# DE-180824.net
KiCad netlist of a schematic drawn in Altium Designer
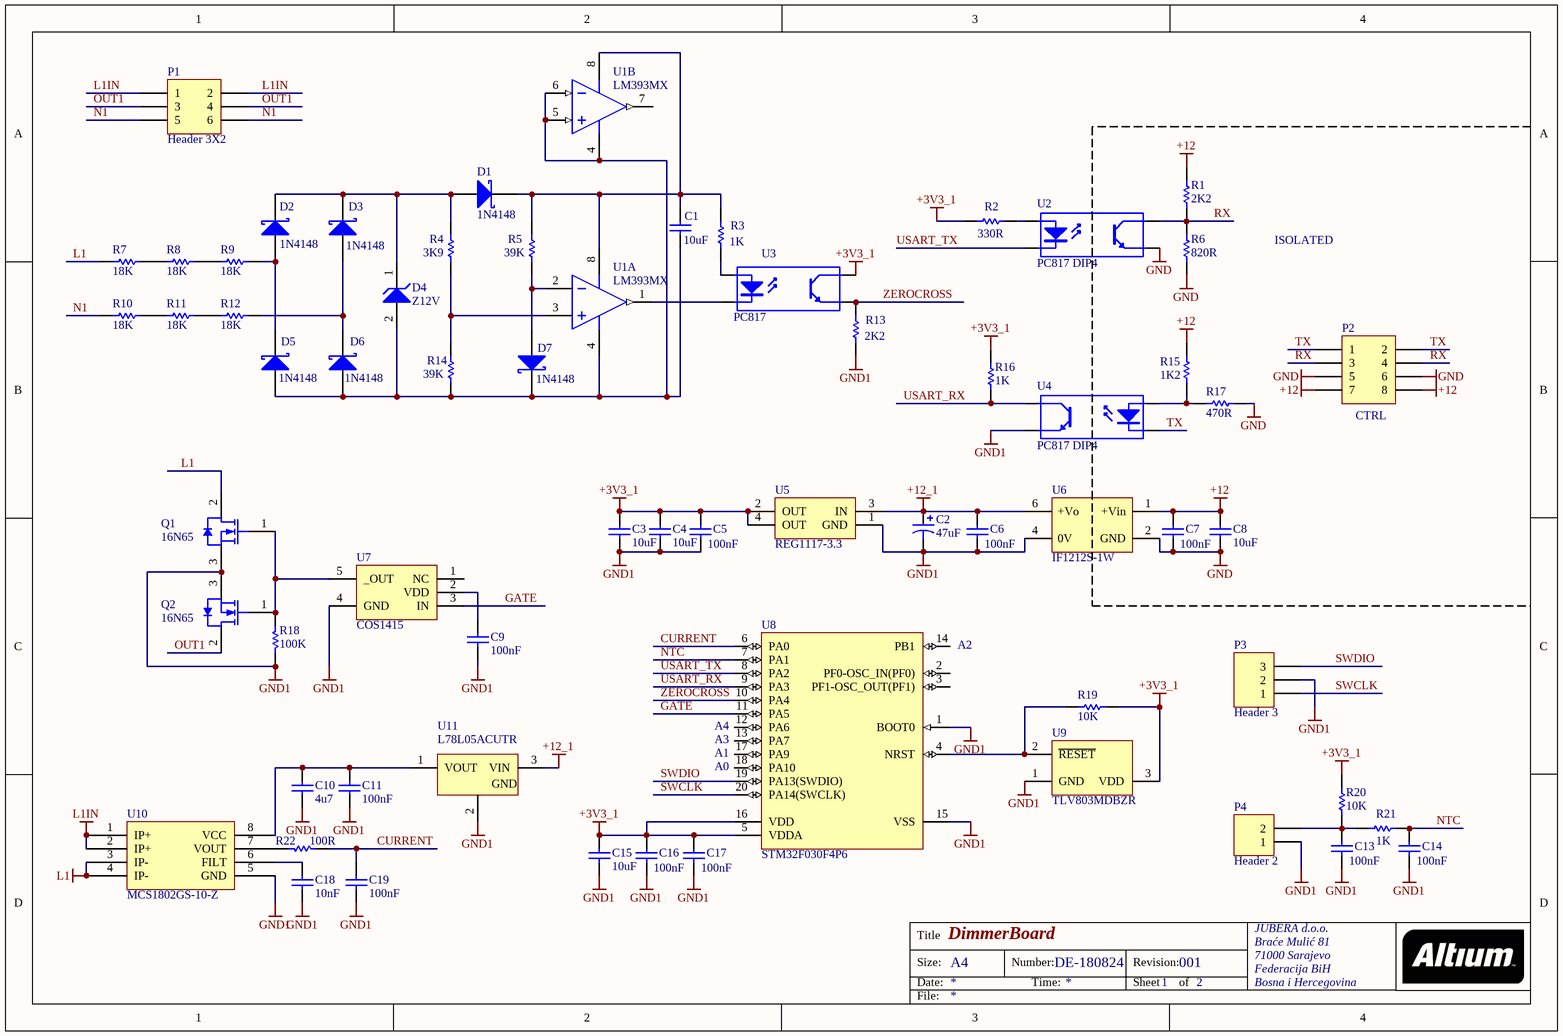
[diagram p0: DE-180824.SchDoc]

(export (version "E")
  (design (tool "Eeschema 10.0.6"))
  (components
    (comp (ref "C1")
      (value "10uF")
      (footprint "0805")
      (description "Ceramic Chip Capacitor - Standard")
      (fields (field (name "PUBLISHER") "Altium Limited"))
      (libsource (lib "DE-100224") (part "C0805"))
    )
    (comp (ref "C2")
      (value "47uF")
      (footprint "H")
      (fields (field (name "PUBLISHER") "Altium Limited"))
      (libsource (lib "Vishay Sprague Tantalum Chip Capacitor") (part "194D476X0015H2"))
    )
    (comp (ref "C3")
      (value "10uF")
      (footprint "0805")
      (description "Ceramic Chip Capacitor - Standard")
      (fields (field (name "Comment") "C0805") (field (name "PUBLISHER") "Altium Limited"))
      (libsource (lib "DE-180824") (part "C0805"))
    )
    (comp (ref "C4")
      (value "10uF")
      (footprint "0805")
      (description "Ceramic Chip Capacitor - Standard")
      (fields (field (name "Comment") "C0805") (field (name "PUBLISHER") "Altium Limited"))
      (libsource (lib "DE-180824") (part "C0805"))
    )
    (comp (ref "C5")
      (value "100nF")
      (footprint "0603")
      (description "Ceramic Chip Capacitor - Standard")
      (fields (field (name "Comment") "C0603") (field (name "PUBLISHER") "Altium Limited"))
      (libsource (lib "DE-180824") (part "C0603"))
    )
    (comp (ref "C6")
      (value "100nF")
      (footprint "0603")
      (description "Ceramic Chip Capacitor - Standard")
      (fields (field (name "Comment") "C0603") (field (name "PUBLISHER") "Altium Limited"))
      (libsource (lib "DE-180824") (part "C0603"))
    )
    (comp (ref "C7")
      (value "100nF")
      (footprint "0603")
      (description "Ceramic Chip Capacitor - Standard")
      (fields (field (name "Comment") "C0603") (field (name "PUBLISHER") "Altium Limited"))
      (libsource (lib "DE-180824") (part "C0603"))
    )
    (comp (ref "C8")
      (value "10uF")
      (footprint "0805")
      (description "Ceramic Chip Capacitor - Standard")
      (fields (field (name "Comment") "C0805") (field (name "PUBLISHER") "Altium Limited"))
      (libsource (lib "DE-180824") (part "C0805"))
    )
    (comp (ref "C9")
      (value "100nF")
      (footprint "0603")
      (description "Ceramic Chip Capacitor - Standard")
      (fields (field (name "Comment") "C0603") (field (name "PUBLISHER") "Altium Limited"))
      (libsource (lib "DE-180824") (part "C0603"))
    )
    (comp (ref "C10")
      (value "4u7")
      (footprint "0805")
      (description "Ceramic Chip Capacitor - Standard")
      (fields (field (name "Comment") "C0805") (field (name "PUBLISHER") "Altium Limited"))
      (libsource (lib "DE-120824") (part "C0805"))
    )
    (comp (ref "C11")
      (value "100nF")
      (footprint "0603")
      (description "Ceramic Chip Capacitor - Standard")
      (fields (field (name "Comment") "C0603") (field (name "PUBLISHER") "Altium Limited"))
      (libsource (lib "DE-120824") (part "C0603"))
    )
    (comp (ref "C13")
      (value "100nF")
      (footprint "0603")
      (description "Ceramic Chip Capacitor - Standard")
      (fields (field (name "Comment") "C0603") (field (name "PUBLISHER") "Altium Limited"))
      (libsource (lib "DE-180824") (part "C0603"))
    )
    (comp (ref "C14")
      (value "100nF")
      (footprint "0603")
      (description "Ceramic Chip Capacitor - Standard")
      (fields (field (name "Comment") "C0603") (field (name "PUBLISHER") "Altium Limited"))
      (libsource (lib "DE-180824") (part "C0603"))
    )
    (comp (ref "C15")
      (value "10uF")
      (footprint "0805")
      (description "Ceramic Chip Capacitor - Standard")
      (fields (field (name "Comment") "C0805") (field (name "PUBLISHER") "Altium Limited"))
      (libsource (lib "DE-180824") (part "C0805"))
    )
    (comp (ref "C16")
      (value "100nF")
      (footprint "0603")
      (description "Ceramic Chip Capacitor - Standard")
      (fields (field (name "Comment") "C0603") (field (name "PUBLISHER") "Altium Limited"))
      (libsource (lib "DE-180824") (part "C0603"))
    )
    (comp (ref "C17")
      (value "100nF")
      (footprint "0603")
      (description "Ceramic Chip Capacitor - Standard")
      (fields (field (name "Comment") "C0603") (field (name "PUBLISHER") "Altium Limited"))
      (libsource (lib "DE-180824") (part "C0603"))
    )
    (comp (ref "C18")
      (value "10nF")
      (footprint "0603")
      (description "Ceramic Chip Capacitor - Standard")
      (fields (field (name "Comment") "C0603") (field (name "PUBLISHER") "Altium Limited"))
      (libsource (lib "DE-120824") (part "C0603"))
    )
    (comp (ref "C19")
      (value "100nF")
      (footprint "0603")
      (description "Ceramic Chip Capacitor - Standard")
      (fields (field (name "Comment") "C0603") (field (name "PUBLISHER") "Altium Limited"))
      (libsource (lib "DE-120824") (part "C0603"))
    )
    (comp (ref "D1")
      (value "1N4148")
      (footprint "SOD323")
      (description "Schottky Barrier Diode")
      (fields (field (name "PUBLISHER") "Altium Limited"))
      (libsource (lib "DE-100224") (part "1PS76SB10"))
    )
    (comp (ref "D2")
      (value "1N4148")
      (footprint "SOD323")
      (description "Schottky Barrier Diode")
      (fields (field (name "PUBLISHER") "Altium Limited"))
      (libsource (lib "DE-100224") (part "1PS76SB10"))
    )
    (comp (ref "D3")
      (value "1N4148")
      (footprint "SOD323")
      (description "Schottky Barrier Diode")
      (fields (field (name "PUBLISHER") "Altium Limited"))
      (libsource (lib "DE-100224") (part "1PS76SB10"))
    )
    (comp (ref "D4")
      (value "Z12V")
      (footprint "ONSC-SOD-323-2-477-02_V")
      (description "Zener Voltage Regulator, 300 mW, 2-Pin SOD-323, Pb-Free, Tape and Reel")
      (fields (field (name "MANUFACTURER") "On Semiconductor") (field (name "PARTNUMBER") "SZMM3Z12VT1G"))
      (libsource (lib "ON Semi Zener Diodes") (part "SZMM3Z12VT1G"))
    )
    (comp (ref "D5")
      (value "1N4148")
      (footprint "SOD323")
      (description "Schottky Barrier Diode")
      (fields (field (name "PUBLISHER") "Altium Limited"))
      (libsource (lib "DE-100224") (part "1PS76SB10"))
    )
    (comp (ref "D6")
      (value "1N4148")
      (footprint "SOD323")
      (description "Schottky Barrier Diode")
      (fields (field (name "PUBLISHER") "Altium Limited"))
      (libsource (lib "DE-100224") (part "1PS76SB10"))
    )
    (comp (ref "D7")
      (value "1N4148")
      (footprint "SOD323")
      (description "Schottky Barrier Diode")
      (fields (field (name "PUBLISHER") "Altium Limited"))
      (libsource (lib "DE-100224") (part "1PS76SB10"))
    )
    (comp (ref "P1")
      (value "Header 3X2")
      (footprint "HDR2X3")
      (description "Header, 3-Pin, Dual row")
      (fields (field (name "PUBLISHER") "Altium Limited"))
      (libsource (lib "Miscellaneous Connectors") (part "Header 3X2"))
    )
    (comp (ref "P2")
      (value "CTRL")
      (footprint "HDR2X4")
      (description "Header, 4-Pin, Dual row")
      (fields (field (name "PUBLISHER") "Altium Limited"))
      (libsource (lib "DE-180824") (part "Header 4X2"))
    )
    (comp (ref "P3")
      (value "Header 3")
      (footprint "HDR1X3")
      (description "Header, 3-Pin")
      (fields (field (name "PUBLISHER") "Altium Limited"))
      (libsource (lib "Miscellaneous Connectors") (part "Header 3"))
    )
    (comp (ref "P4")
      (value "Header 2")
      (footprint "HDR1X2")
      (description "Header, 2-Pin")
      (fields (field (name "PUBLISHER") "Altium Limited"))
      (libsource (lib "Miscellaneous Connectors") (part "Header 2"))
    )
    (comp (ref "Q1")
      (value "16N65")
      (footprint "INF-PG-TO263-3-2_N")
      (fields (field (name "MANUFACTURER") "Infineon") (field (name "PARTNUMBER") "IPB020NE7N3 G"))
      (libsource (lib "Infineon_Power_MOSFET") (part "IPB020NE7N3 G"))
    )
    (comp (ref "Q2")
      (value "16N65")
      (footprint "INF-PG-TO263-3-2_N")
      (fields (field (name "MANUFACTURER") "Infineon") (field (name "PARTNUMBER") "IPB020NE7N3 G"))
      (libsource (lib "Infineon_Power_MOSFET") (part "IPB020NE7N3 G"))
    )
    (comp (ref "R1")
      (value "2K2")
      (footprint "ERA-0603")
      (fields (field (name "PUBLISHER") "Altium Limited"))
      (libsource (lib "DE-100224") (part "ERAV"))
    )
    (comp (ref "R2")
      (value "330R")
      (footprint "ERA-0603")
      (fields (field (name "PUBLISHER") "Altium Limited"))
      (libsource (lib "DE-100224") (part "ERAV"))
    )
    (comp (ref "R3")
      (value "1K")
      (footprint "ERA-0603")
      (fields (field (name "PUBLISHER") "Altium Limited"))
      (libsource (lib "DE-100224") (part "ERAV"))
    )
    (comp (ref "R4")
      (value "3K9")
      (footprint "ERA-0603")
      (fields (field (name "PUBLISHER") "Altium Limited"))
      (libsource (lib "DE-100224") (part "ERAV"))
    )
    (comp (ref "R5")
      (value "39K")
      (footprint "ERA-0603")
      (fields (field (name "PUBLISHER") "Altium Limited"))
      (libsource (lib "DE-100224") (part "ERAV"))
    )
    (comp (ref "R6")
      (value "820R")
      (footprint "ERA-0603")
      (fields (field (name "PUBLISHER") "Altium Limited"))
      (libsource (lib "DE-100224") (part "ERAV"))
    )
    (comp (ref "R7")
      (value "18K")
      (footprint "ERA-0805")
      (fields (field (name "PUBLISHER") "Altium Limited"))
      (libsource (lib "DE-100224") (part "ERAS"))
    )
    (comp (ref "R8")
      (value "18K")
      (footprint "ERA-0805")
      (fields (field (name "PUBLISHER") "Altium Limited"))
      (libsource (lib "DE-100224") (part "ERAS"))
    )
    (comp (ref "R9")
      (value "18K")
      (footprint "ERA-0805")
      (fields (field (name "PUBLISHER") "Altium Limited"))
      (libsource (lib "DE-100224") (part "ERAS"))
    )
    (comp (ref "R10")
      (value "18K")
      (footprint "ERA-0805")
      (fields (field (name "PUBLISHER") "Altium Limited"))
      (libsource (lib "DE-100224") (part "ERAS"))
    )
    (comp (ref "R11")
      (value "18K")
      (footprint "ERA-0805")
      (fields (field (name "PUBLISHER") "Altium Limited"))
      (libsource (lib "DE-100224") (part "ERAS"))
    )
    (comp (ref "R12")
      (value "18K")
      (footprint "ERA-0805")
      (fields (field (name "PUBLISHER") "Altium Limited"))
      (libsource (lib "DE-100224") (part "ERAS"))
    )
    (comp (ref "R13")
      (value "2K2")
      (footprint "ERA-0603")
      (fields (field (name "PUBLISHER") "Altium Limited"))
      (libsource (lib "DE-100224") (part "ERAV"))
    )
    (comp (ref "R14")
      (value "39K")
      (footprint "ERA-0603")
      (fields (field (name "PUBLISHER") "Altium Limited"))
      (libsource (lib "DE-100224") (part "ERAV"))
    )
    (comp (ref "R15")
      (value "1K2")
      (footprint "ERA-0603")
      (fields (field (name "PUBLISHER") "Altium Limited"))
      (libsource (lib "DE-100224") (part "ERAV"))
    )
    (comp (ref "R16")
      (value "1K")
      (footprint "ERA-0603")
      (fields (field (name "PUBLISHER") "Altium Limited"))
      (libsource (lib "DE-100224") (part "ERAV"))
    )
    (comp (ref "R17")
      (value "470R")
      (footprint "ERA-0603")
      (fields (field (name "PUBLISHER") "Altium Limited"))
      (libsource (lib "DE-100224") (part "ERAV"))
    )
    (comp (ref "R18")
      (value "100K")
      (footprint "ERA-0805")
      (fields (field (name "PUBLISHER") "Altium Limited"))
      (libsource (lib "DE-180824") (part "ERAS"))
    )
    (comp (ref "R19")
      (value "10K")
      (footprint "ERA-0603")
      (fields (field (name "PUBLISHER") "Altium Limited"))
      (libsource (lib "DE-180824") (part "ERA3Y"))
    )
    (comp (ref "R20")
      (value "10K")
      (footprint "ERA-0603")
      (fields (field (name "PUBLISHER") "Altium Limited"))
      (libsource (lib "DE-180824") (part "ERA3Y"))
    )
    (comp (ref "R21")
      (value "1K")
      (footprint "ERA-0603")
      (fields (field (name "PUBLISHER") "Altium Limited"))
      (libsource (lib "DE-180824") (part "ERA3Y"))
    )
    (comp (ref "R22")
      (value "100R")
      (footprint "ERA-0603")
      (fields (field (name "PUBLISHER") "Altium Limited"))
      (libsource (lib "DE-220817") (part "ERAV"))
    )
    (comp (ref "U1")
      (value "LM393MX")
      (footprint "M08A_N")
      (description "Low Power Low Offset Voltage Dual Comparator, 8-pin Narrow SOIC")
      (fields (field (name "MANUFACTURER") "National Semiconductor"))
      (libsource (lib "National Semiconductor Comparator") (part "LM393MX"))
    )
    (comp (ref "U2")
      (value "PC817 DIP4")
      (footprint "DIP-4")
      (description "4-Pin Phototransistor Optocoupler")
      (fields (field (name "PUBLISHER") "Altium Limited"))
      (libsource (lib "DE-180824") (part "PC817 DIP4"))
    )
    (comp (ref "U3")
      (value "PC817")
      (footprint "DIP-4")
      (description "4-Pin Phototransistor Optocoupler")
      (fields (field (name "PUBLISHER") "Altium Limited"))
      (libsource (lib "DE-100224") (part "PC817"))
    )
    (comp (ref "U4")
      (value "PC817 DIP4")
      (footprint "DIP-4")
      (description "4-Pin Phototransistor Optocoupler")
      (fields (field (name "PUBLISHER") "Altium Limited"))
      (libsource (lib "DE-180824") (part "PC817 DIP4"))
    )
    (comp (ref "U5")
      (value "REG1117-3.3")
      (footprint "ZZ311")
      (description "800mA and 1A Low Dropout Positive Regulator 2.85V, 3.3V, 5V, and Adjustable")
      (fields (field (name "PUBLISHER") "Altium Limited"))
      (libsource (lib "DE-180824") (part "REG1117-3.3"))
    )
    (comp (ref "U6")
      (value "IF1212S-1W")
      (footprint "IF1212S-1W")
      (description "1W isolated dc dc converter")
      (libsource (lib "DE-180824") (part "IF1212S-1W"))
    )
    (comp (ref "U7")
      (value "COS1415")
      (footprint "SOT23-5")
      (description "1.5A Single-Channel\r\nHigh-Speed Power MOSFETDriver")
      (libsource (lib "DE-180824") (part "COS1415"))
    )
    (comp (ref "U8")
      (value "STM32F030F4P6")
      (footprint "STM-TSSOP20_N")
      (libsource (lib "STMicroelectronics STM32 F0") (part "STM32F030F4P6"))
    )
    (comp (ref "U9")
      (value "TLV803MDBZR")
      (footprint "DBZ3_N")
      (fields (field (name "MANUFACTURER") "Texas Instruments"))
      (libsource (lib "TI Power Management Supervisor and Reset IC") (part "TLV803MDBZR"))
    )
    (comp (ref "U10")
      (value "MCS1802GS-10-Z")
      (footprint "SOIC-SN8_N")
      (libsource (lib "DE-120824") (part "ACS71240"))
    )
    (comp (ref "U11")
      (value "L78L05ACUTR")
      (footprint "SOT-89_N")
      (description "Positive Voltage Regulator, 5V, 4-Pin SOT-89, Tape and Reel")
      (libsource (lib "DE-180824") (part "L78L05ACUTR"))
    )
  )
  (nets
    (net (code "1") (name "+3V3_1") (class "Default")
      (node (ref "C15") (pin "2") (pinfunction "2_2") (pintype "passive"))
      (node (ref "C16") (pin "2") (pinfunction "2_2") (pintype "passive"))
      (node (ref "C17") (pin "2") (pinfunction "2_2") (pintype "passive"))
      (node (ref "C3") (pin "2") (pinfunction "2_2") (pintype "passive"))
      (node (ref "C4") (pin "2") (pinfunction "2_2") (pintype "passive"))
      (node (ref "C5") (pin "2") (pinfunction "2_2") (pintype "passive"))
      (node (ref "R16") (pin "2") (pinfunction "2_2") (pintype "passive"))
      (node (ref "R19") (pin "2") (pinfunction "2_2") (pintype "passive"))
      (node (ref "R2") (pin "2") (pinfunction "2_2") (pintype "passive"))
      (node (ref "R20") (pin "2") (pinfunction "2_2") (pintype "passive"))
      (node (ref "U3") (pin "4") (pinfunction "C_4") (pintype "passive"))
      (node (ref "U5") (pin "2") (pinfunction "OUT_2") (pintype "power_in"))
      (node (ref "U5") (pin "4") (pinfunction "OUT_4") (pintype "power_in"))
      (node (ref "U8") (pin "16") (pinfunction "VDD_16") (pintype "power_in"))
      (node (ref "U8") (pin "5") (pinfunction "VDDA_5") (pintype "power_in"))
      (node (ref "U9") (pin "3") (pinfunction "VDD_3") (pintype "power_in"))
    )
    (net (code "2") (name "+12") (class "Default")
      (node (ref "C7") (pin "2") (pinfunction "2_2") (pintype "passive"))
      (node (ref "C8") (pin "2") (pinfunction "2_2") (pintype "passive"))
      (node (ref "P2") (pin "7") (pinfunction "7_7") (pintype "passive"))
      (node (ref "P2") (pin "8") (pinfunction "8_8") (pintype "passive"))
      (node (ref "R1") (pin "1") (pinfunction "1_1") (pintype "passive"))
      (node (ref "R15") (pin "1") (pinfunction "1_1") (pintype "passive"))
      (node (ref "U6") (pin "1") (pinfunction "+Vin_1") (pintype "passive"))
    )
    (net (code "3") (name "+12_1") (class "Default")
      (node (ref "C2") (pin "1") (pinfunction "1_1") (pintype "passive"))
      (node (ref "C6") (pin "2") (pinfunction "2_2") (pintype "passive"))
      (node (ref "U11") (pin "3") (pinfunction "VIN_3") (pintype "power_in"))
      (node (ref "U5") (pin "3") (pinfunction "IN_3") (pintype "power_in"))
      (node (ref "U6") (pin "6") (pinfunction "+Vo_6") (pintype "passive"))
    )
    (net (code "4") (name "/CURRENT") (class "Default")
      (node (ref "C19") (pin "2") (pinfunction "2_2") (pintype "passive"))
      (node (ref "R22") (pin "1") (pinfunction "1_1") (pintype "passive"))
      (node (ref "U8") (pin "6") (pinfunction "PA0_6") (pintype "bidirectional"))
    )
    (net (code "5") (name "/GATE") (class "Default")
      (node (ref "U7") (pin "3") (pinfunction "IN_3") (pintype "passive"))
      (node (ref "U8") (pin "11") (pinfunction "PA5_11") (pintype "bidirectional"))
    )
    (net (code "6") (name "/N1") (class "Default")
      (node (ref "P1") (pin "5") (pinfunction "5_5") (pintype "passive"))
      (node (ref "P1") (pin "6") (pinfunction "6_6") (pintype "passive"))
      (node (ref "R10") (pin "1") (pinfunction "1_1") (pintype "passive"))
    )
    (net (code "7") (name "/NTC") (class "Default")
      (node (ref "C14") (pin "2") (pinfunction "2_2") (pintype "passive"))
      (node (ref "R21") (pin "1") (pinfunction "1_1") (pintype "passive"))
      (node (ref "U8") (pin "7") (pinfunction "PA1_7") (pintype "bidirectional"))
    )
    (net (code "8") (name "/OUT1") (class "Default")
      (node (ref "P1") (pin "3") (pinfunction "3_3") (pintype "passive"))
      (node (ref "P1") (pin "4") (pinfunction "4_4") (pintype "passive"))
      (node (ref "Q2") (pin "2") (pinfunction "DRAIN_2") (pintype "passive"))
    )
    (net (code "9") (name "/RX") (class "Default")
      (node (ref "P2") (pin "3") (pinfunction "3_3") (pintype "passive"))
      (node (ref "P2") (pin "4") (pinfunction "4_4") (pintype "passive"))
      (node (ref "R1") (pin "2") (pinfunction "2_2") (pintype "passive"))
      (node (ref "R6") (pin "1") (pinfunction "1_1") (pintype "passive"))
      (node (ref "U2") (pin "4") (pinfunction "C_4") (pintype "passive"))
    )
    (net (code "10") (name "/SWCLK") (class "Default")
      (node (ref "P3") (pin "1") (pinfunction "1_1") (pintype "passive"))
      (node (ref "U8") (pin "20") (pinfunction "PA14(SWCLK)_20") (pintype "bidirectional"))
    )
    (net (code "11") (name "/SWDIO") (class "Default")
      (node (ref "P3") (pin "3") (pinfunction "3_3") (pintype "passive"))
      (node (ref "U8") (pin "19") (pinfunction "PA13(SWDIO)_19") (pintype "bidirectional"))
    )
    (net (code "12") (name "/TX") (class "Default")
      (node (ref "P2") (pin "1") (pinfunction "1_1") (pintype "passive"))
      (node (ref "P2") (pin "2") (pinfunction "2_2") (pintype "passive"))
      (node (ref "U4") (pin "2") (pinfunction "K_2") (pintype "passive"))
    )
    (net (code "13") (name "/USART_RX") (class "Default")
      (node (ref "R16") (pin "1") (pinfunction "1_1") (pintype "passive"))
      (node (ref "U4") (pin "4") (pinfunction "C_4") (pintype "passive"))
      (node (ref "U8") (pin "9") (pinfunction "PA3_9") (pintype "bidirectional"))
    )
    (net (code "14") (name "/USART_TX") (class "Default")
      (node (ref "U2") (pin "2") (pinfunction "K_2") (pintype "passive"))
      (node (ref "U8") (pin "8") (pinfunction "PA2_8") (pintype "bidirectional"))
    )
    (net (code "15") (name "/ZEROCROSS") (class "Default")
      (node (ref "R13") (pin "2") (pinfunction "2_2") (pintype "passive"))
      (node (ref "U3") (pin "3") (pinfunction "E_3") (pintype "passive"))
      (node (ref "U8") (pin "10") (pinfunction "PA4_10") (pintype "bidirectional"))
    )
    (net (code "16") (name "GND") (class "Default")
      (node (ref "C7") (pin "1") (pinfunction "1_1") (pintype "passive"))
      (node (ref "C8") (pin "1") (pinfunction "1_1") (pintype "passive"))
      (node (ref "P2") (pin "5") (pinfunction "5_5") (pintype "passive"))
      (node (ref "P2") (pin "6") (pinfunction "6_6") (pintype "passive"))
      (node (ref "R17") (pin "2") (pinfunction "2_2") (pintype "passive"))
      (node (ref "R6") (pin "2") (pinfunction "2_2") (pintype "passive"))
      (node (ref "U2") (pin "3") (pinfunction "E_3") (pintype "passive"))
      (node (ref "U6") (pin "2") (pinfunction "GND_2") (pintype "passive"))
    )
    (net (code "17") (name "GND1") (class "Default")
      (node (ref "C10") (pin "1") (pinfunction "1_1") (pintype "passive"))
      (node (ref "C11") (pin "1") (pinfunction "1_1") (pintype "passive"))
      (node (ref "C13") (pin "1") (pinfunction "1_1") (pintype "passive"))
      (node (ref "C14") (pin "1") (pinfunction "1_1") (pintype "passive"))
      (node (ref "C15") (pin "1") (pinfunction "1_1") (pintype "passive"))
      (node (ref "C16") (pin "1") (pinfunction "1_1") (pintype "passive"))
      (node (ref "C17") (pin "1") (pinfunction "1_1") (pintype "passive"))
      (node (ref "C18") (pin "1") (pinfunction "1_1") (pintype "passive"))
      (node (ref "C19") (pin "1") (pinfunction "1_1") (pintype "passive"))
      (node (ref "C2") (pin "2") (pinfunction "2_2") (pintype "passive"))
      (node (ref "C3") (pin "1") (pinfunction "1_1") (pintype "passive"))
      (node (ref "C4") (pin "1") (pinfunction "1_1") (pintype "passive"))
      (node (ref "C5") (pin "1") (pinfunction "1_1") (pintype "passive"))
      (node (ref "C6") (pin "1") (pinfunction "1_1") (pintype "passive"))
      (node (ref "C9") (pin "1") (pinfunction "1_1") (pintype "passive"))
      (node (ref "P3") (pin "2") (pinfunction "2_2") (pintype "passive"))
      (node (ref "P4") (pin "1") (pinfunction "1_1") (pintype "passive"))
      (node (ref "Q1") (pin "3") (pinfunction "SOURCE_3") (pintype "passive"))
      (node (ref "Q2") (pin "3") (pinfunction "SOURCE_3") (pintype "passive"))
      (node (ref "R13") (pin "1") (pinfunction "1_1") (pintype "passive"))
      (node (ref "R18") (pin "1") (pinfunction "1_1") (pintype "passive"))
      (node (ref "U10") (pin "5") (pinfunction "GND_5") (pintype "passive"))
      (node (ref "U11") (pin "2") (pinfunction "GND_2") (pintype "power_in"))
      (node (ref "U4") (pin "3") (pinfunction "E_3") (pintype "passive"))
      (node (ref "U5") (pin "1") (pinfunction "GND_1") (pintype "power_in"))
      (node (ref "U6") (pin "4") (pinfunction "0V_4") (pintype "passive"))
      (node (ref "U7") (pin "4") (pinfunction "GND_4") (pintype "passive"))
      (node (ref "U8") (pin "1") (pinfunction "BOOT0_1") (pintype "input"))
      (node (ref "U8") (pin "15") (pinfunction "VSS_15") (pintype "power_in"))
      (node (ref "U9") (pin "1") (pinfunction "GND_1") (pintype "power_in"))
    )
    (net (code "18") (name "L1") (class "Default")
      (node (ref "Q1") (pin "2") (pinfunction "DRAIN_2") (pintype "passive"))
      (node (ref "R7") (pin "1") (pinfunction "1_1") (pintype "passive"))
      (node (ref "U10") (pin "3") (pinfunction "IP-_3") (pintype "passive"))
      (node (ref "U10") (pin "4") (pinfunction "IP-_4") (pintype "passive"))
    )
    (net (code "19") (name "L1IN") (class "Default")
      (node (ref "P1") (pin "1") (pinfunction "1_1") (pintype "passive"))
      (node (ref "P1") (pin "2") (pinfunction "2_2") (pintype "passive"))
      (node (ref "U10") (pin "1") (pinfunction "IP+_1") (pintype "passive"))
      (node (ref "U10") (pin "2") (pinfunction "IP+_2") (pintype "passive"))
    )
    (net (code "20") (name "Net-(C13-Pad2)") (class "Default")
      (node (ref "C13") (pin "2") (pinfunction "2_2") (pintype "passive"))
      (node (ref "P4") (pin "2") (pinfunction "2_2") (pintype "passive"))
      (node (ref "R20") (pin "1") (pinfunction "1_1") (pintype "passive"))
      (node (ref "R21") (pin "2") (pinfunction "2_2") (pintype "passive"))
    )
    (net (code "21") (name "Net-(D1-A)") (class "Default")
      (node (ref "D1") (pin "2") (pinfunction "A_2") (pintype "passive"))
      (node (ref "D2") (pin "1") (pinfunction "K_1") (pintype "passive"))
      (node (ref "D3") (pin "1") (pinfunction "K_1") (pintype "passive"))
      (node (ref "D4") (pin "1") (pinfunction "K_1") (pintype "passive"))
      (node (ref "R4") (pin "2") (pinfunction "2_2") (pintype "passive"))
    )
    (net (code "22") (name "Net-(D1-K)") (class "Default")
      (node (ref "C1") (pin "2") (pinfunction "2_2") (pintype "passive"))
      (node (ref "D1") (pin "1") (pinfunction "K_1") (pintype "passive"))
      (node (ref "R3") (pin "2") (pinfunction "2_2") (pintype "passive"))
      (node (ref "R5") (pin "2") (pinfunction "2_2") (pintype "passive"))
      (node (ref "U1") (pin "8") (pinfunction "V+_8") (pintype "power_in"))
    )
    (net (code "23") (name "Net-(D2-A)") (class "Default")
      (node (ref "D2") (pin "2") (pinfunction "A_2") (pintype "passive"))
      (node (ref "D5") (pin "1") (pinfunction "K_1") (pintype "passive"))
      (node (ref "R9") (pin "2") (pinfunction "2_2") (pintype "passive"))
    )
    (net (code "24") (name "Net-(D3-A)") (class "Default")
      (node (ref "D3") (pin "2") (pinfunction "A_2") (pintype "passive"))
      (node (ref "D6") (pin "1") (pinfunction "K_1") (pintype "passive"))
      (node (ref "R12") (pin "2") (pinfunction "2_2") (pintype "passive"))
    )
    (net (code "25") (name "Net-(D4-A)") (class "Default")
      (node (ref "C1") (pin "1") (pinfunction "1_1") (pintype "passive"))
      (node (ref "D4") (pin "2") (pinfunction "A_2") (pintype "passive"))
      (node (ref "D5") (pin "2") (pinfunction "A_2") (pintype "passive"))
      (node (ref "D6") (pin "2") (pinfunction "A_2") (pintype "passive"))
      (node (ref "D7") (pin "1") (pinfunction "K_1") (pintype "passive"))
      (node (ref "R14") (pin "1") (pinfunction "1_1") (pintype "passive"))
      (node (ref "U1") (pin "4") (pinfunction "GND_4") (pintype "power_in"))
      (node (ref "U1") (pin "5") (pinfunction "INB+_5") (pintype "passive"))
      (node (ref "U1") (pin "6") (pinfunction "INB-_6") (pintype "passive"))
    )
    (net (code "26") (name "Net-(D7-A)") (class "Default")
      (node (ref "D7") (pin "2") (pinfunction "A_2") (pintype "passive"))
      (node (ref "R5") (pin "1") (pinfunction "1_1") (pintype "passive"))
      (node (ref "U1") (pin "2") (pinfunction "INA-_2") (pintype "passive"))
    )
    (net (code "27") (name "Net-(Q1-GATE)") (class "Default")
      (node (ref "Q1") (pin "1") (pinfunction "GATE_1") (pintype "passive"))
      (node (ref "Q2") (pin "1") (pinfunction "GATE_1") (pintype "passive"))
      (node (ref "R18") (pin "2") (pinfunction "2_2") (pintype "passive"))
      (node (ref "U7") (pin "5") (pinfunction "_OUT_5") (pintype "passive"))
    )
    (net (code "28") (name "Net-(R7-Pad2)") (class "Default")
      (node (ref "R7") (pin "2") (pinfunction "2_2") (pintype "passive"))
      (node (ref "R8") (pin "1") (pinfunction "1_1") (pintype "passive"))
    )
    (net (code "29") (name "Net-(R8-Pad2)") (class "Default")
      (node (ref "R8") (pin "2") (pinfunction "2_2") (pintype "passive"))
      (node (ref "R9") (pin "1") (pinfunction "1_1") (pintype "passive"))
    )
    (net (code "30") (name "Net-(R10-Pad2)") (class "Default")
      (node (ref "R10") (pin "2") (pinfunction "2_2") (pintype "passive"))
      (node (ref "R11") (pin "1") (pinfunction "1_1") (pintype "passive"))
    )
    (net (code "31") (name "Net-(R11-Pad2)") (class "Default")
      (node (ref "R11") (pin "2") (pinfunction "2_2") (pintype "passive"))
      (node (ref "R12") (pin "1") (pinfunction "1_1") (pintype "passive"))
    )
    (net (code "32") (name "Net-(U1A-INA+)") (class "Default")
      (node (ref "R14") (pin "2") (pinfunction "2_2") (pintype "passive"))
      (node (ref "R4") (pin "1") (pinfunction "1_1") (pintype "passive"))
      (node (ref "U1") (pin "3") (pinfunction "INA+_3") (pintype "passive"))
    )
    (net (code "33") (name "Net-(U1A-OUTA)") (class "Default")
      (node (ref "U1") (pin "1") (pinfunction "OUTA_1") (pintype "output"))
      (node (ref "U3") (pin "2") (pinfunction "K_2") (pintype "passive"))
    )
    (net (code "34") (name "Net-(U2-A)") (class "Default")
      (node (ref "R2") (pin "1") (pinfunction "1_1") (pintype "passive"))
      (node (ref "U2") (pin "1") (pinfunction "A_1") (pintype "passive"))
    )
    (net (code "35") (name "Net-(U3-A)") (class "Default")
      (node (ref "R3") (pin "1") (pinfunction "1_1") (pintype "passive"))
      (node (ref "U3") (pin "1") (pinfunction "A_1") (pintype "passive"))
    )
    (net (code "36") (name "Net-(U4-A)") (class "Default")
      (node (ref "R15") (pin "2") (pinfunction "2_2") (pintype "passive"))
      (node (ref "R17") (pin "1") (pinfunction "1_1") (pintype "passive"))
      (node (ref "U4") (pin "1") (pinfunction "A_1") (pintype "passive"))
    )
    (net (code "37") (name "Net-(U7-VDD)") (class "Default")
      (node (ref "C9") (pin "2") (pinfunction "2_2") (pintype "passive"))
      (node (ref "U7") (pin "2") (pinfunction "VDD_2") (pintype "passive"))
    )
    (net (code "38") (name "Net-(U8-NRST)") (class "Default")
      (node (ref "R19") (pin "1") (pinfunction "1_1") (pintype "passive"))
      (node (ref "U8") (pin "4") (pinfunction "NRST_4") (pintype "bidirectional"))
      (node (ref "U9") (pin "2") (pinfunction "~{RESET}_2") (pintype "open_collector"))
    )
    (net (code "39") (name "Net-(U10-FILT)") (class "Default")
      (node (ref "C18") (pin "2") (pinfunction "2_2") (pintype "passive"))
      (node (ref "U10") (pin "6") (pinfunction "FILT_6") (pintype "passive"))
    )
    (net (code "40") (name "Net-(U10-VCC)") (class "Default")
      (node (ref "C10") (pin "2") (pinfunction "2_2") (pintype "passive"))
      (node (ref "C11") (pin "2") (pinfunction "2_2") (pintype "passive"))
      (node (ref "U10") (pin "8") (pinfunction "VCC_8") (pintype "passive"))
      (node (ref "U11") (pin "1") (pinfunction "VOUT_1") (pintype "power_in"))
    )
    (net (code "41") (name "Net-(U10-VOUT)") (class "Default")
      (node (ref "R22") (pin "2") (pinfunction "2_2") (pintype "passive"))
      (node (ref "U10") (pin "7") (pinfunction "VOUT_7") (pintype "passive"))
    )
    (net (code "42") (name "unconnected-(U1B-OUTB-Pad7)") (class "Default")
      (node (ref "U1") (pin "7") (pinfunction "OUTB_7") (pintype "output"))
    )
    (net (code "43") (name "unconnected-(U7-NC-Pad1)") (class "Default")
      (node (ref "U7") (pin "1") (pinfunction "NC_1") (pintype "passive"))
    )
    (net (code "44") (name "unconnected-(U8-PA6-Pad12)") (class "Default")
      (node (ref "U8") (pin "12") (pinfunction "PA6_12") (pintype "bidirectional"))
    )
    (net (code "45") (name "unconnected-(U8-PA7-Pad13)") (class "Default")
      (node (ref "U8") (pin "13") (pinfunction "PA7_13") (pintype "bidirectional"))
    )
    (net (code "46") (name "unconnected-(U8-PA9-Pad17)") (class "Default")
      (node (ref "U8") (pin "17") (pinfunction "PA9_17") (pintype "bidirectional"))
    )
    (net (code "47") (name "unconnected-(U8-PA10-Pad18)") (class "Default")
      (node (ref "U8") (pin "18") (pinfunction "PA10_18") (pintype "bidirectional"))
    )
    (net (code "48") (name "unconnected-(U8-PB1-Pad14)") (class "Default")
      (node (ref "U8") (pin "14") (pinfunction "PB1_14") (pintype "bidirectional"))
    )
    (net (code "49") (name "unconnected-(U8-PF0-OSC_IN(PF0)-Pad2)") (class "Default")
      (node (ref "U8") (pin "2") (pinfunction "PF0-OSC_IN(PF0)_2") (pintype "bidirectional"))
    )
    (net (code "50") (name "unconnected-(U8-PF1-OSC_OUT(PF1)-Pad3)") (class "Default")
      (node (ref "U8") (pin "3") (pinfunction "PF1-OSC_OUT(PF1)_3") (pintype "bidirectional"))
    )
  )
)
